# Easy_Check_rev2_chip_tray.net
KiCad netlist of a schematic drawn in EAGLE
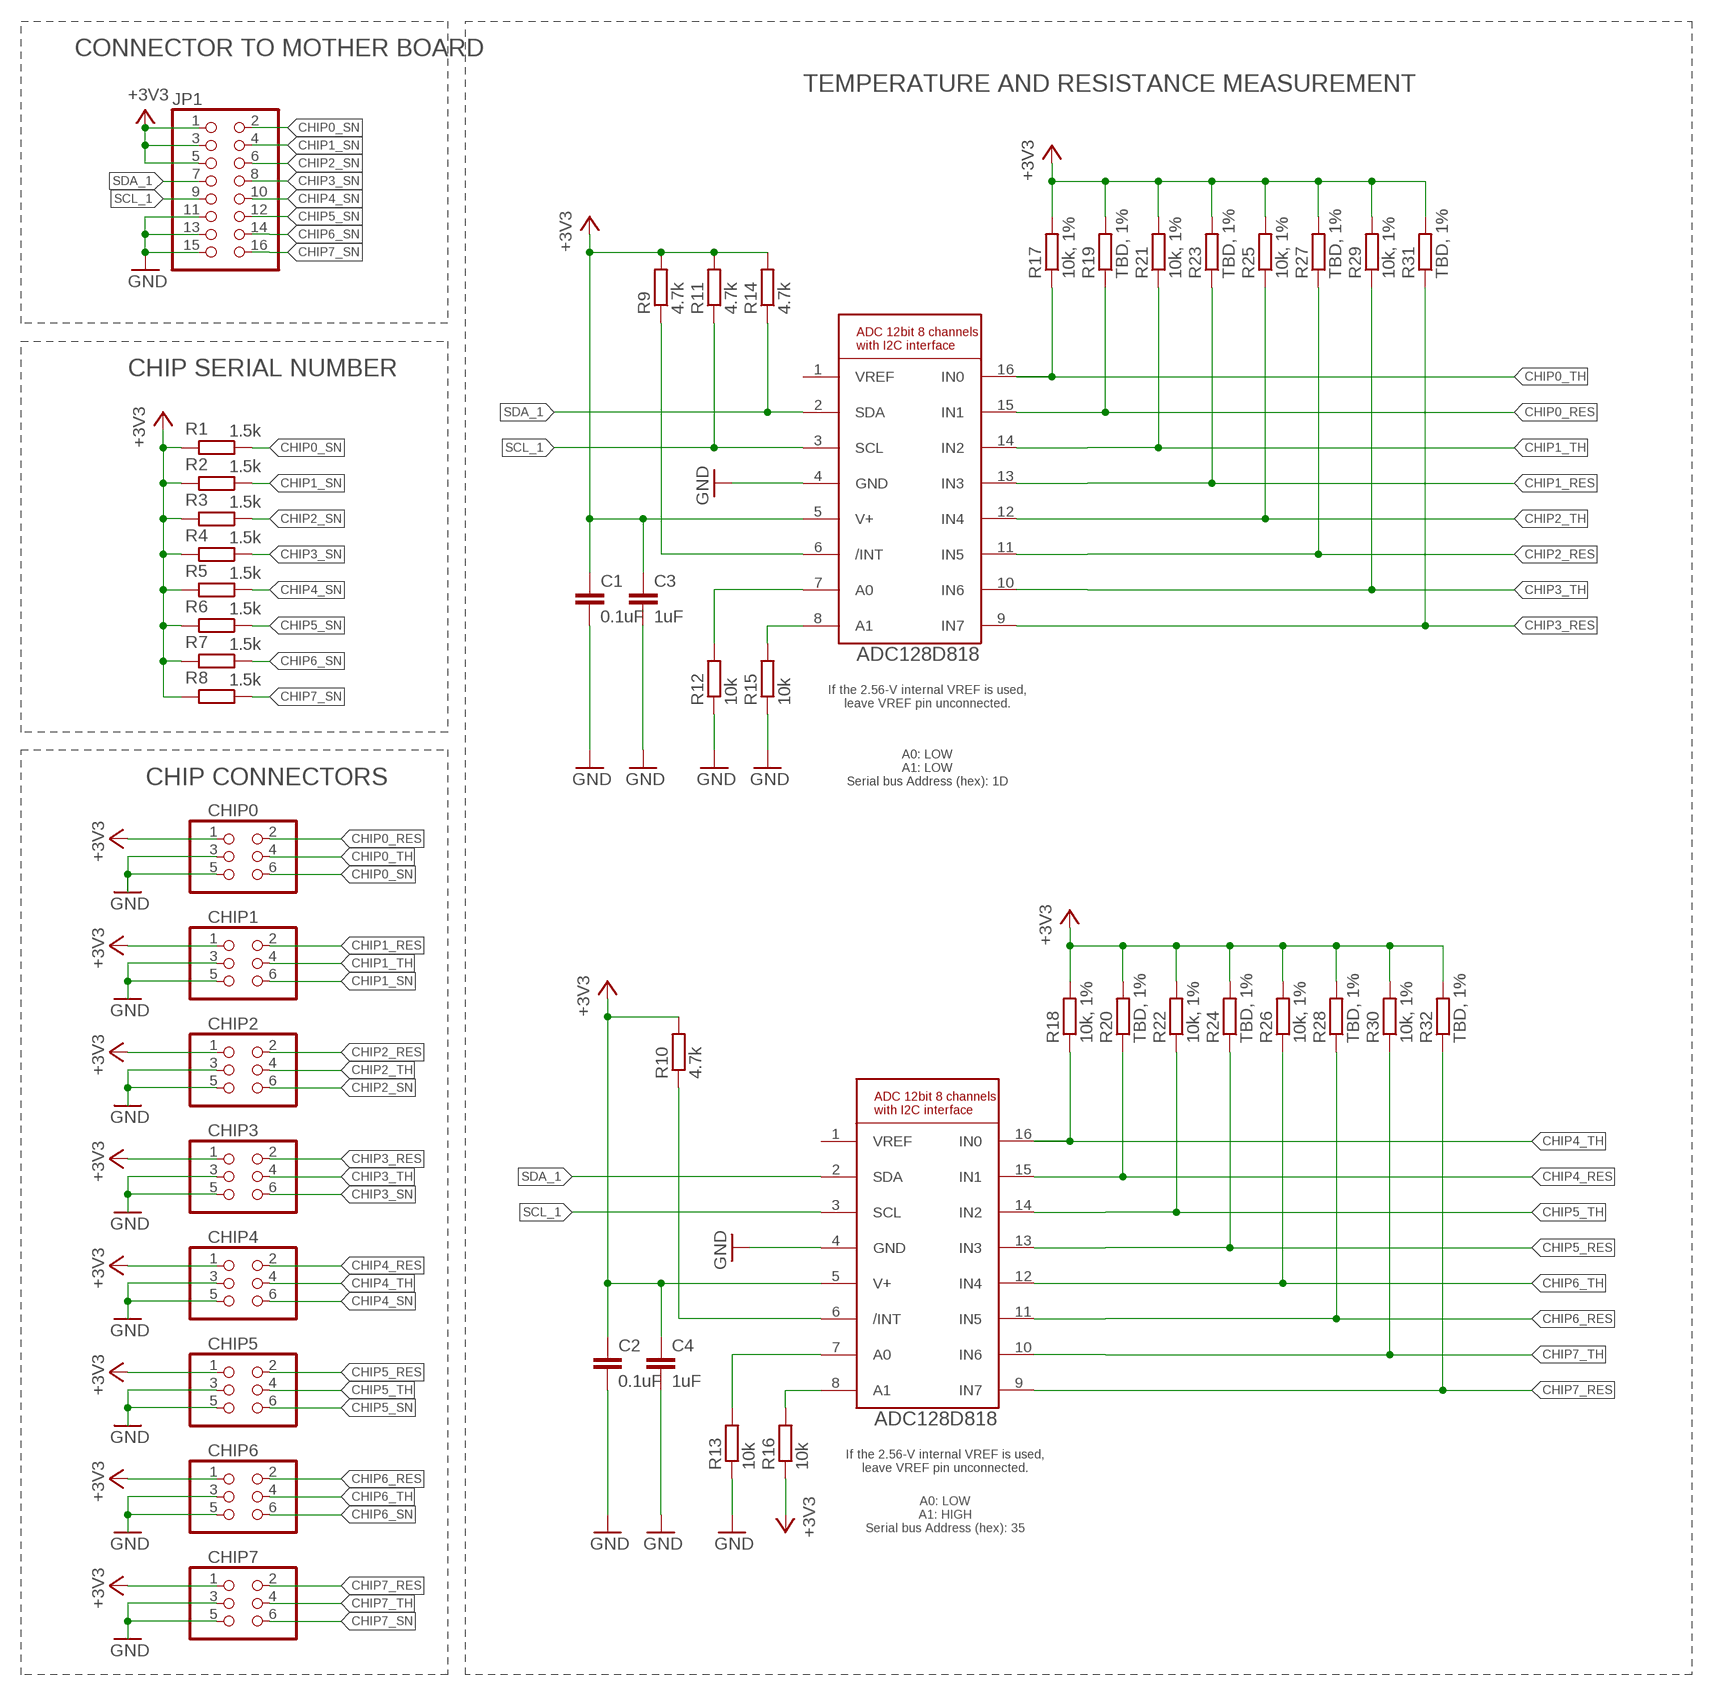
[diagram p0: schematic, sheet 1]

(export (version "E")
  (design (tool "Eeschema 10.0.6"))
  (components
    (comp (ref "C1")
      (value "0.1uF")
      (footprint "eagle-import:C0603")
      (libsource (lib "eagle-import") (part "C-EUC0603"))
    )
    (comp (ref "C2")
      (value "0.1uF")
      (footprint "eagle-import:C0603")
      (libsource (lib "eagle-import") (part "C-EUC0603"))
    )
    (comp (ref "C3")
      (value "1uF")
      (footprint "eagle-import:C0603")
      (libsource (lib "eagle-import") (part "C-EUC0603"))
    )
    (comp (ref "C4")
      (value "1uF")
      (footprint "eagle-import:C0603")
      (libsource (lib "eagle-import") (part "C-EUC0603"))
    )
    (comp (ref "CHIP0")
      (value "PINHD-2X3")
      (footprint "eagle-import:2X03")
      (libsource (lib "eagle-import") (part "PINHD-2X3"))
    )
    (comp (ref "CHIP1")
      (value "PINHD-2X3")
      (footprint "eagle-import:2X03")
      (libsource (lib "eagle-import") (part "PINHD-2X3"))
    )
    (comp (ref "CHIP2")
      (value "PINHD-2X3")
      (footprint "eagle-import:2X03")
      (libsource (lib "eagle-import") (part "PINHD-2X3"))
    )
    (comp (ref "CHIP3")
      (value "PINHD-2X3")
      (footprint "eagle-import:2X03")
      (libsource (lib "eagle-import") (part "PINHD-2X3"))
    )
    (comp (ref "CHIP4")
      (value "PINHD-2X3")
      (footprint "eagle-import:2X03")
      (libsource (lib "eagle-import") (part "PINHD-2X3"))
    )
    (comp (ref "CHIP5")
      (value "PINHD-2X3")
      (footprint "eagle-import:2X03")
      (libsource (lib "eagle-import") (part "PINHD-2X3"))
    )
    (comp (ref "CHIP6")
      (value "PINHD-2X3")
      (footprint "eagle-import:2X03")
      (libsource (lib "eagle-import") (part "PINHD-2X3"))
    )
    (comp (ref "CHIP7")
      (value "PINHD-2X3")
      (footprint "eagle-import:2X03")
      (libsource (lib "eagle-import") (part "PINHD-2X3"))
    )
    (comp (ref "JP1")
      (value "PINHD-2X8")
      (footprint "eagle-import:2X08")
      (libsource (lib "eagle-import") (part "PINHD-2X8"))
    )
    (comp (ref "R1")
      (value "1.5k")
      (footprint "eagle-import:R0603")
      (libsource (lib "eagle-import") (part "R-EU_R0603"))
    )
    (comp (ref "R2")
      (value "1.5k")
      (footprint "eagle-import:R0603")
      (libsource (lib "eagle-import") (part "R-EU_R0603"))
    )
    (comp (ref "R3")
      (value "1.5k")
      (footprint "eagle-import:R0603")
      (libsource (lib "eagle-import") (part "R-EU_R0603"))
    )
    (comp (ref "R4")
      (value "1.5k")
      (footprint "eagle-import:R0603")
      (libsource (lib "eagle-import") (part "R-EU_R0603"))
    )
    (comp (ref "R5")
      (value "1.5k")
      (footprint "eagle-import:R0603")
      (libsource (lib "eagle-import") (part "R-EU_R0603"))
    )
    (comp (ref "R6")
      (value "1.5k")
      (footprint "eagle-import:R0603")
      (libsource (lib "eagle-import") (part "R-EU_R0603"))
    )
    (comp (ref "R7")
      (value "1.5k")
      (footprint "eagle-import:R0603")
      (libsource (lib "eagle-import") (part "R-EU_R0603"))
    )
    (comp (ref "R8")
      (value "1.5k")
      (footprint "eagle-import:R0603")
      (libsource (lib "eagle-import") (part "R-EU_R0603"))
    )
    (comp (ref "R9")
      (value "4.7k")
      (footprint "eagle-import:R0603")
      (libsource (lib "eagle-import") (part "R-EU_R0603"))
    )
    (comp (ref "R10")
      (value "4.7k")
      (footprint "eagle-import:R0603")
      (libsource (lib "eagle-import") (part "R-EU_R0603"))
    )
    (comp (ref "R11")
      (value "4.7k")
      (footprint "eagle-import:R0603")
      (libsource (lib "eagle-import") (part "R-EU_R0603"))
    )
    (comp (ref "R12")
      (value "10k")
      (footprint "eagle-import:R0603")
      (libsource (lib "eagle-import") (part "R-EU_R0603"))
    )
    (comp (ref "R13")
      (value "10k")
      (footprint "eagle-import:R0603")
      (libsource (lib "eagle-import") (part "R-EU_R0603"))
    )
    (comp (ref "R14")
      (value "4.7k")
      (footprint "eagle-import:R0603")
      (libsource (lib "eagle-import") (part "R-EU_R0603"))
    )
    (comp (ref "R15")
      (value "10k")
      (footprint "eagle-import:R0603")
      (libsource (lib "eagle-import") (part "R-EU_R0603"))
    )
    (comp (ref "R16")
      (value "10k")
      (footprint "eagle-import:R0603")
      (libsource (lib "eagle-import") (part "R-EU_R0603"))
    )
    (comp (ref "R17")
      (value "10k, 1%")
      (footprint "eagle-import:R0603")
      (libsource (lib "eagle-import") (part "R-EU_R0603"))
    )
    (comp (ref "R18")
      (value "10k, 1%")
      (footprint "eagle-import:R0603")
      (libsource (lib "eagle-import") (part "R-EU_R0603"))
    )
    (comp (ref "R19")
      (value "TBD, 1%")
      (footprint "eagle-import:R0603")
      (libsource (lib "eagle-import") (part "R-EU_R0603"))
    )
    (comp (ref "R20")
      (value "TBD, 1%")
      (footprint "eagle-import:R0603")
      (libsource (lib "eagle-import") (part "R-EU_R0603"))
    )
    (comp (ref "R21")
      (value "10k, 1%")
      (footprint "eagle-import:R0603")
      (libsource (lib "eagle-import") (part "R-EU_R0603"))
    )
    (comp (ref "R22")
      (value "10k, 1%")
      (footprint "eagle-import:R0603")
      (libsource (lib "eagle-import") (part "R-EU_R0603"))
    )
    (comp (ref "R23")
      (value "TBD, 1%")
      (footprint "eagle-import:R0603")
      (libsource (lib "eagle-import") (part "R-EU_R0603"))
    )
    (comp (ref "R24")
      (value "TBD, 1%")
      (footprint "eagle-import:R0603")
      (libsource (lib "eagle-import") (part "R-EU_R0603"))
    )
    (comp (ref "R25")
      (value "10k, 1%")
      (footprint "eagle-import:R0603")
      (libsource (lib "eagle-import") (part "R-EU_R0603"))
    )
    (comp (ref "R26")
      (value "10k, 1%")
      (footprint "eagle-import:R0603")
      (libsource (lib "eagle-import") (part "R-EU_R0603"))
    )
    (comp (ref "R27")
      (value "TBD, 1%")
      (footprint "eagle-import:R0603")
      (libsource (lib "eagle-import") (part "R-EU_R0603"))
    )
    (comp (ref "R28")
      (value "TBD, 1%")
      (footprint "eagle-import:R0603")
      (libsource (lib "eagle-import") (part "R-EU_R0603"))
    )
    (comp (ref "R29")
      (value "10k, 1%")
      (footprint "eagle-import:R0603")
      (libsource (lib "eagle-import") (part "R-EU_R0603"))
    )
    (comp (ref "R30")
      (value "10k, 1%")
      (footprint "eagle-import:R0603")
      (libsource (lib "eagle-import") (part "R-EU_R0603"))
    )
    (comp (ref "R31")
      (value "TBD, 1%")
      (footprint "eagle-import:R0603")
      (libsource (lib "eagle-import") (part "R-EU_R0603"))
    )
    (comp (ref "R32")
      (value "TBD, 1%")
      (footprint "eagle-import:R0603")
      (libsource (lib "eagle-import") (part "R-EU_R0603"))
    )
    (comp (ref "U1")
      (value "LMD128D818")
      (footprint "eagle-import:ADC128D818")
      (libsource (lib "eagle-import") (part "LMD128D818"))
    )
    (comp (ref "U2")
      (value "LMD128D818")
      (footprint "eagle-import:ADC128D818")
      (libsource (lib "eagle-import") (part "LMD128D818"))
    )
  )
  (nets
    (net (code "1") (name "+3V3") (class "Default")
      (node (ref "C1") (pin "1") (pinfunction "1_1") (pintype "passive"))
      (node (ref "C2") (pin "1") (pinfunction "1_1") (pintype "passive"))
      (node (ref "C3") (pin "1") (pinfunction "1_1") (pintype "passive"))
      (node (ref "C4") (pin "1") (pinfunction "1_1") (pintype "passive"))
      (node (ref "CHIP0") (pin "1") (pinfunction "1_1") (pintype "passive"))
      (node (ref "CHIP1") (pin "1") (pinfunction "1_1") (pintype "passive"))
      (node (ref "CHIP2") (pin "1") (pinfunction "1_1") (pintype "passive"))
      (node (ref "CHIP3") (pin "1") (pinfunction "1_1") (pintype "passive"))
      (node (ref "CHIP4") (pin "1") (pinfunction "1_1") (pintype "passive"))
      (node (ref "CHIP5") (pin "1") (pinfunction "1_1") (pintype "passive"))
      (node (ref "CHIP6") (pin "1") (pinfunction "1_1") (pintype "passive"))
      (node (ref "CHIP7") (pin "1") (pinfunction "1_1") (pintype "passive"))
      (node (ref "JP1") (pin "1") (pinfunction "1_1") (pintype "passive"))
      (node (ref "JP1") (pin "3") (pinfunction "3_3") (pintype "passive"))
      (node (ref "JP1") (pin "5") (pinfunction "5_5") (pintype "passive"))
      (node (ref "R1") (pin "2") (pinfunction "2_2") (pintype "passive"))
      (node (ref "R10") (pin "2") (pinfunction "2_2") (pintype "passive"))
      (node (ref "R11") (pin "2") (pinfunction "2_2") (pintype "passive"))
      (node (ref "R14") (pin "2") (pinfunction "2_2") (pintype "passive"))
      (node (ref "R16") (pin "1") (pinfunction "1_1") (pintype "passive"))
      (node (ref "R17") (pin "2") (pinfunction "2_2") (pintype "passive"))
      (node (ref "R18") (pin "2") (pinfunction "2_2") (pintype "passive"))
      (node (ref "R19") (pin "2") (pinfunction "2_2") (pintype "passive"))
      (node (ref "R2") (pin "2") (pinfunction "2_2") (pintype "passive"))
      (node (ref "R20") (pin "2") (pinfunction "2_2") (pintype "passive"))
      (node (ref "R21") (pin "2") (pinfunction "2_2") (pintype "passive"))
      (node (ref "R22") (pin "2") (pinfunction "2_2") (pintype "passive"))
      (node (ref "R23") (pin "2") (pinfunction "2_2") (pintype "passive"))
      (node (ref "R24") (pin "2") (pinfunction "2_2") (pintype "passive"))
      (node (ref "R25") (pin "2") (pinfunction "2_2") (pintype "passive"))
      (node (ref "R26") (pin "2") (pinfunction "2_2") (pintype "passive"))
      (node (ref "R27") (pin "2") (pinfunction "2_2") (pintype "passive"))
      (node (ref "R28") (pin "2") (pinfunction "2_2") (pintype "passive"))
      (node (ref "R29") (pin "2") (pinfunction "2_2") (pintype "passive"))
      (node (ref "R3") (pin "2") (pinfunction "2_2") (pintype "passive"))
      (node (ref "R30") (pin "2") (pinfunction "2_2") (pintype "passive"))
      (node (ref "R31") (pin "2") (pinfunction "2_2") (pintype "passive"))
      (node (ref "R32") (pin "2") (pinfunction "2_2") (pintype "passive"))
      (node (ref "R4") (pin "2") (pinfunction "2_2") (pintype "passive"))
      (node (ref "R5") (pin "2") (pinfunction "2_2") (pintype "passive"))
      (node (ref "R6") (pin "2") (pinfunction "2_2") (pintype "passive"))
      (node (ref "R7") (pin "2") (pinfunction "2_2") (pintype "passive"))
      (node (ref "R8") (pin "2") (pinfunction "2_2") (pintype "passive"))
      (node (ref "R9") (pin "2") (pinfunction "2_2") (pintype "passive"))
      (node (ref "U1") (pin "5") (pinfunction "V+_5") (pintype "bidirectional"))
      (node (ref "U2") (pin "5") (pinfunction "V+_5") (pintype "bidirectional"))
    )
    (net (code "2") (name "CHIP0_RES") (class "Default")
      (node (ref "CHIP0") (pin "2") (pinfunction "2_2") (pintype "passive"))
      (node (ref "R19") (pin "1") (pinfunction "1_1") (pintype "passive"))
      (node (ref "U1") (pin "15") (pinfunction "IN1_15") (pintype "bidirectional"))
    )
    (net (code "3") (name "CHIP0_SN") (class "Default")
      (node (ref "CHIP0") (pin "6") (pinfunction "6_6") (pintype "passive"))
      (node (ref "JP1") (pin "2") (pinfunction "2_2") (pintype "passive"))
      (node (ref "R1") (pin "1") (pinfunction "1_1") (pintype "passive"))
    )
    (net (code "4") (name "CHIP0_TH") (class "Default")
      (node (ref "CHIP0") (pin "4") (pinfunction "4_4") (pintype "passive"))
      (node (ref "R17") (pin "1") (pinfunction "1_1") (pintype "passive"))
      (node (ref "U1") (pin "16") (pinfunction "IN0_16") (pintype "bidirectional"))
    )
    (net (code "5") (name "CHIP1_RES") (class "Default")
      (node (ref "CHIP1") (pin "2") (pinfunction "2_2") (pintype "passive"))
      (node (ref "R23") (pin "1") (pinfunction "1_1") (pintype "passive"))
      (node (ref "U1") (pin "13") (pinfunction "IN3_13") (pintype "bidirectional"))
    )
    (net (code "6") (name "CHIP1_SN") (class "Default")
      (node (ref "CHIP1") (pin "6") (pinfunction "6_6") (pintype "passive"))
      (node (ref "JP1") (pin "4") (pinfunction "4_4") (pintype "passive"))
      (node (ref "R2") (pin "1") (pinfunction "1_1") (pintype "passive"))
    )
    (net (code "7") (name "CHIP1_TH") (class "Default")
      (node (ref "CHIP1") (pin "4") (pinfunction "4_4") (pintype "passive"))
      (node (ref "R21") (pin "1") (pinfunction "1_1") (pintype "passive"))
      (node (ref "U1") (pin "14") (pinfunction "IN2_14") (pintype "bidirectional"))
    )
    (net (code "8") (name "CHIP2_RES") (class "Default")
      (node (ref "CHIP2") (pin "2") (pinfunction "2_2") (pintype "passive"))
      (node (ref "R27") (pin "1") (pinfunction "1_1") (pintype "passive"))
      (node (ref "U1") (pin "11") (pinfunction "IN5_11") (pintype "bidirectional"))
    )
    (net (code "9") (name "CHIP2_SN") (class "Default")
      (node (ref "CHIP2") (pin "6") (pinfunction "6_6") (pintype "passive"))
      (node (ref "JP1") (pin "6") (pinfunction "6_6") (pintype "passive"))
      (node (ref "R3") (pin "1") (pinfunction "1_1") (pintype "passive"))
    )
    (net (code "10") (name "CHIP2_TH") (class "Default")
      (node (ref "CHIP2") (pin "4") (pinfunction "4_4") (pintype "passive"))
      (node (ref "R25") (pin "1") (pinfunction "1_1") (pintype "passive"))
      (node (ref "U1") (pin "12") (pinfunction "IN4_12") (pintype "bidirectional"))
    )
    (net (code "11") (name "CHIP3_RES") (class "Default")
      (node (ref "CHIP3") (pin "2") (pinfunction "2_2") (pintype "passive"))
      (node (ref "R31") (pin "1") (pinfunction "1_1") (pintype "passive"))
      (node (ref "U1") (pin "9") (pinfunction "IN7_9") (pintype "bidirectional"))
    )
    (net (code "12") (name "CHIP3_SN") (class "Default")
      (node (ref "CHIP3") (pin "6") (pinfunction "6_6") (pintype "passive"))
      (node (ref "JP1") (pin "8") (pinfunction "8_8") (pintype "passive"))
      (node (ref "R4") (pin "1") (pinfunction "1_1") (pintype "passive"))
    )
    (net (code "13") (name "CHIP3_TH") (class "Default")
      (node (ref "CHIP3") (pin "4") (pinfunction "4_4") (pintype "passive"))
      (node (ref "R29") (pin "1") (pinfunction "1_1") (pintype "passive"))
      (node (ref "U1") (pin "10") (pinfunction "IN6_10") (pintype "bidirectional"))
    )
    (net (code "14") (name "CHIP4_RES") (class "Default")
      (node (ref "CHIP4") (pin "2") (pinfunction "2_2") (pintype "passive"))
      (node (ref "R20") (pin "1") (pinfunction "1_1") (pintype "passive"))
      (node (ref "U2") (pin "15") (pinfunction "IN1_15") (pintype "bidirectional"))
    )
    (net (code "15") (name "CHIP4_SN") (class "Default")
      (node (ref "CHIP4") (pin "6") (pinfunction "6_6") (pintype "passive"))
      (node (ref "JP1") (pin "10") (pinfunction "10_10") (pintype "passive"))
      (node (ref "R5") (pin "1") (pinfunction "1_1") (pintype "passive"))
    )
    (net (code "16") (name "CHIP4_TH") (class "Default")
      (node (ref "CHIP4") (pin "4") (pinfunction "4_4") (pintype "passive"))
      (node (ref "R18") (pin "1") (pinfunction "1_1") (pintype "passive"))
      (node (ref "U2") (pin "16") (pinfunction "IN0_16") (pintype "bidirectional"))
    )
    (net (code "17") (name "CHIP5_RES") (class "Default")
      (node (ref "CHIP5") (pin "2") (pinfunction "2_2") (pintype "passive"))
      (node (ref "R24") (pin "1") (pinfunction "1_1") (pintype "passive"))
      (node (ref "U2") (pin "13") (pinfunction "IN3_13") (pintype "bidirectional"))
    )
    (net (code "18") (name "CHIP5_SN") (class "Default")
      (node (ref "CHIP5") (pin "6") (pinfunction "6_6") (pintype "passive"))
      (node (ref "JP1") (pin "12") (pinfunction "12_12") (pintype "passive"))
      (node (ref "R6") (pin "1") (pinfunction "1_1") (pintype "passive"))
    )
    (net (code "19") (name "CHIP5_TH") (class "Default")
      (node (ref "CHIP5") (pin "4") (pinfunction "4_4") (pintype "passive"))
      (node (ref "R22") (pin "1") (pinfunction "1_1") (pintype "passive"))
      (node (ref "U2") (pin "14") (pinfunction "IN2_14") (pintype "bidirectional"))
    )
    (net (code "20") (name "CHIP6_RES") (class "Default")
      (node (ref "CHIP6") (pin "2") (pinfunction "2_2") (pintype "passive"))
      (node (ref "R28") (pin "1") (pinfunction "1_1") (pintype "passive"))
      (node (ref "U2") (pin "11") (pinfunction "IN5_11") (pintype "bidirectional"))
    )
    (net (code "21") (name "CHIP6_SN") (class "Default")
      (node (ref "CHIP6") (pin "6") (pinfunction "6_6") (pintype "passive"))
      (node (ref "JP1") (pin "14") (pinfunction "14_14") (pintype "passive"))
      (node (ref "R7") (pin "1") (pinfunction "1_1") (pintype "passive"))
    )
    (net (code "22") (name "CHIP6_TH") (class "Default")
      (node (ref "CHIP6") (pin "4") (pinfunction "4_4") (pintype "passive"))
      (node (ref "R26") (pin "1") (pinfunction "1_1") (pintype "passive"))
      (node (ref "U2") (pin "12") (pinfunction "IN4_12") (pintype "bidirectional"))
    )
    (net (code "23") (name "CHIP7_RES") (class "Default")
      (node (ref "CHIP7") (pin "2") (pinfunction "2_2") (pintype "passive"))
      (node (ref "R32") (pin "1") (pinfunction "1_1") (pintype "passive"))
      (node (ref "U2") (pin "9") (pinfunction "IN7_9") (pintype "bidirectional"))
    )
    (net (code "24") (name "CHIP7_SN") (class "Default")
      (node (ref "CHIP7") (pin "6") (pinfunction "6_6") (pintype "passive"))
      (node (ref "JP1") (pin "16") (pinfunction "16_16") (pintype "passive"))
      (node (ref "R8") (pin "1") (pinfunction "1_1") (pintype "passive"))
    )
    (net (code "25") (name "CHIP7_TH") (class "Default")
      (node (ref "CHIP7") (pin "4") (pinfunction "4_4") (pintype "passive"))
      (node (ref "R30") (pin "1") (pinfunction "1_1") (pintype "passive"))
      (node (ref "U2") (pin "10") (pinfunction "IN6_10") (pintype "bidirectional"))
    )
    (net (code "26") (name "GND") (class "Default")
      (node (ref "C1") (pin "2") (pinfunction "2_2") (pintype "passive"))
      (node (ref "C2") (pin "2") (pinfunction "2_2") (pintype "passive"))
      (node (ref "C3") (pin "2") (pinfunction "2_2") (pintype "passive"))
      (node (ref "C4") (pin "2") (pinfunction "2_2") (pintype "passive"))
      (node (ref "CHIP0") (pin "3") (pinfunction "3_3") (pintype "passive"))
      (node (ref "CHIP0") (pin "5") (pinfunction "5_5") (pintype "passive"))
      (node (ref "CHIP1") (pin "3") (pinfunction "3_3") (pintype "passive"))
      (node (ref "CHIP1") (pin "5") (pinfunction "5_5") (pintype "passive"))
      (node (ref "CHIP2") (pin "3") (pinfunction "3_3") (pintype "passive"))
      (node (ref "CHIP2") (pin "5") (pinfunction "5_5") (pintype "passive"))
      (node (ref "CHIP3") (pin "3") (pinfunction "3_3") (pintype "passive"))
      (node (ref "CHIP3") (pin "5") (pinfunction "5_5") (pintype "passive"))
      (node (ref "CHIP4") (pin "3") (pinfunction "3_3") (pintype "passive"))
      (node (ref "CHIP4") (pin "5") (pinfunction "5_5") (pintype "passive"))
      (node (ref "CHIP5") (pin "3") (pinfunction "3_3") (pintype "passive"))
      (node (ref "CHIP5") (pin "5") (pinfunction "5_5") (pintype "passive"))
      (node (ref "CHIP6") (pin "3") (pinfunction "3_3") (pintype "passive"))
      (node (ref "CHIP6") (pin "5") (pinfunction "5_5") (pintype "passive"))
      (node (ref "CHIP7") (pin "3") (pinfunction "3_3") (pintype "passive"))
      (node (ref "CHIP7") (pin "5") (pinfunction "5_5") (pintype "passive"))
      (node (ref "JP1") (pin "11") (pinfunction "11_11") (pintype "passive"))
      (node (ref "JP1") (pin "13") (pinfunction "13_13") (pintype "passive"))
      (node (ref "JP1") (pin "15") (pinfunction "15_15") (pintype "passive"))
      (node (ref "R12") (pin "1") (pinfunction "1_1") (pintype "passive"))
      (node (ref "R13") (pin "1") (pinfunction "1_1") (pintype "passive"))
      (node (ref "R15") (pin "1") (pinfunction "1_1") (pintype "passive"))
      (node (ref "U1") (pin "4") (pinfunction "GND_4") (pintype "bidirectional"))
      (node (ref "U2") (pin "4") (pinfunction "GND_4") (pintype "bidirectional"))
    )
    (net (code "27") (name "Net-(U1-A0)") (class "Default")
      (node (ref "R12") (pin "2") (pinfunction "2_2") (pintype "passive"))
      (node (ref "U1") (pin "7") (pinfunction "A0_7") (pintype "bidirectional"))
    )
    (net (code "28") (name "Net-(U1-A1)") (class "Default")
      (node (ref "R15") (pin "2") (pinfunction "2_2") (pintype "passive"))
      (node (ref "U1") (pin "8") (pinfunction "A1_8") (pintype "bidirectional"))
    )
    (net (code "29") (name "Net-(U1-{slash}INT)") (class "Default")
      (node (ref "R9") (pin "1") (pinfunction "1_1") (pintype "passive"))
      (node (ref "U1") (pin "6") (pinfunction "/INT_6") (pintype "bidirectional"))
    )
    (net (code "30") (name "Net-(U2-A0)") (class "Default")
      (node (ref "R13") (pin "2") (pinfunction "2_2") (pintype "passive"))
      (node (ref "U2") (pin "7") (pinfunction "A0_7") (pintype "bidirectional"))
    )
    (net (code "31") (name "Net-(U2-A1)") (class "Default")
      (node (ref "R16") (pin "2") (pinfunction "2_2") (pintype "passive"))
      (node (ref "U2") (pin "8") (pinfunction "A1_8") (pintype "bidirectional"))
    )
    (net (code "32") (name "Net-(U2-{slash}INT)") (class "Default")
      (node (ref "R10") (pin "1") (pinfunction "1_1") (pintype "passive"))
      (node (ref "U2") (pin "6") (pinfunction "/INT_6") (pintype "bidirectional"))
    )
    (net (code "33") (name "SCL_1") (class "Default")
      (node (ref "JP1") (pin "9") (pinfunction "9_9") (pintype "passive"))
      (node (ref "R11") (pin "1") (pinfunction "1_1") (pintype "passive"))
      (node (ref "U1") (pin "3") (pinfunction "SCL_3") (pintype "bidirectional"))
      (node (ref "U2") (pin "3") (pinfunction "SCL_3") (pintype "bidirectional"))
    )
    (net (code "34") (name "SDA_1") (class "Default")
      (node (ref "JP1") (pin "7") (pinfunction "7_7") (pintype "passive"))
      (node (ref "R14") (pin "1") (pinfunction "1_1") (pintype "passive"))
      (node (ref "U1") (pin "2") (pinfunction "SDA_2") (pintype "bidirectional"))
      (node (ref "U2") (pin "2") (pinfunction "SDA_2") (pintype "bidirectional"))
    )
    (net (code "35") (name "unconnected-(U1-VREF-Pad1)") (class "Default")
      (node (ref "U1") (pin "1") (pinfunction "VREF_1") (pintype "bidirectional"))
    )
    (net (code "36") (name "unconnected-(U2-VREF-Pad1)") (class "Default")
      (node (ref "U2") (pin "1") (pinfunction "VREF_1") (pintype "bidirectional"))
    )
  )
)
